# spindle_light.net
KiCad netlist of a schematic drawn in EAGLE
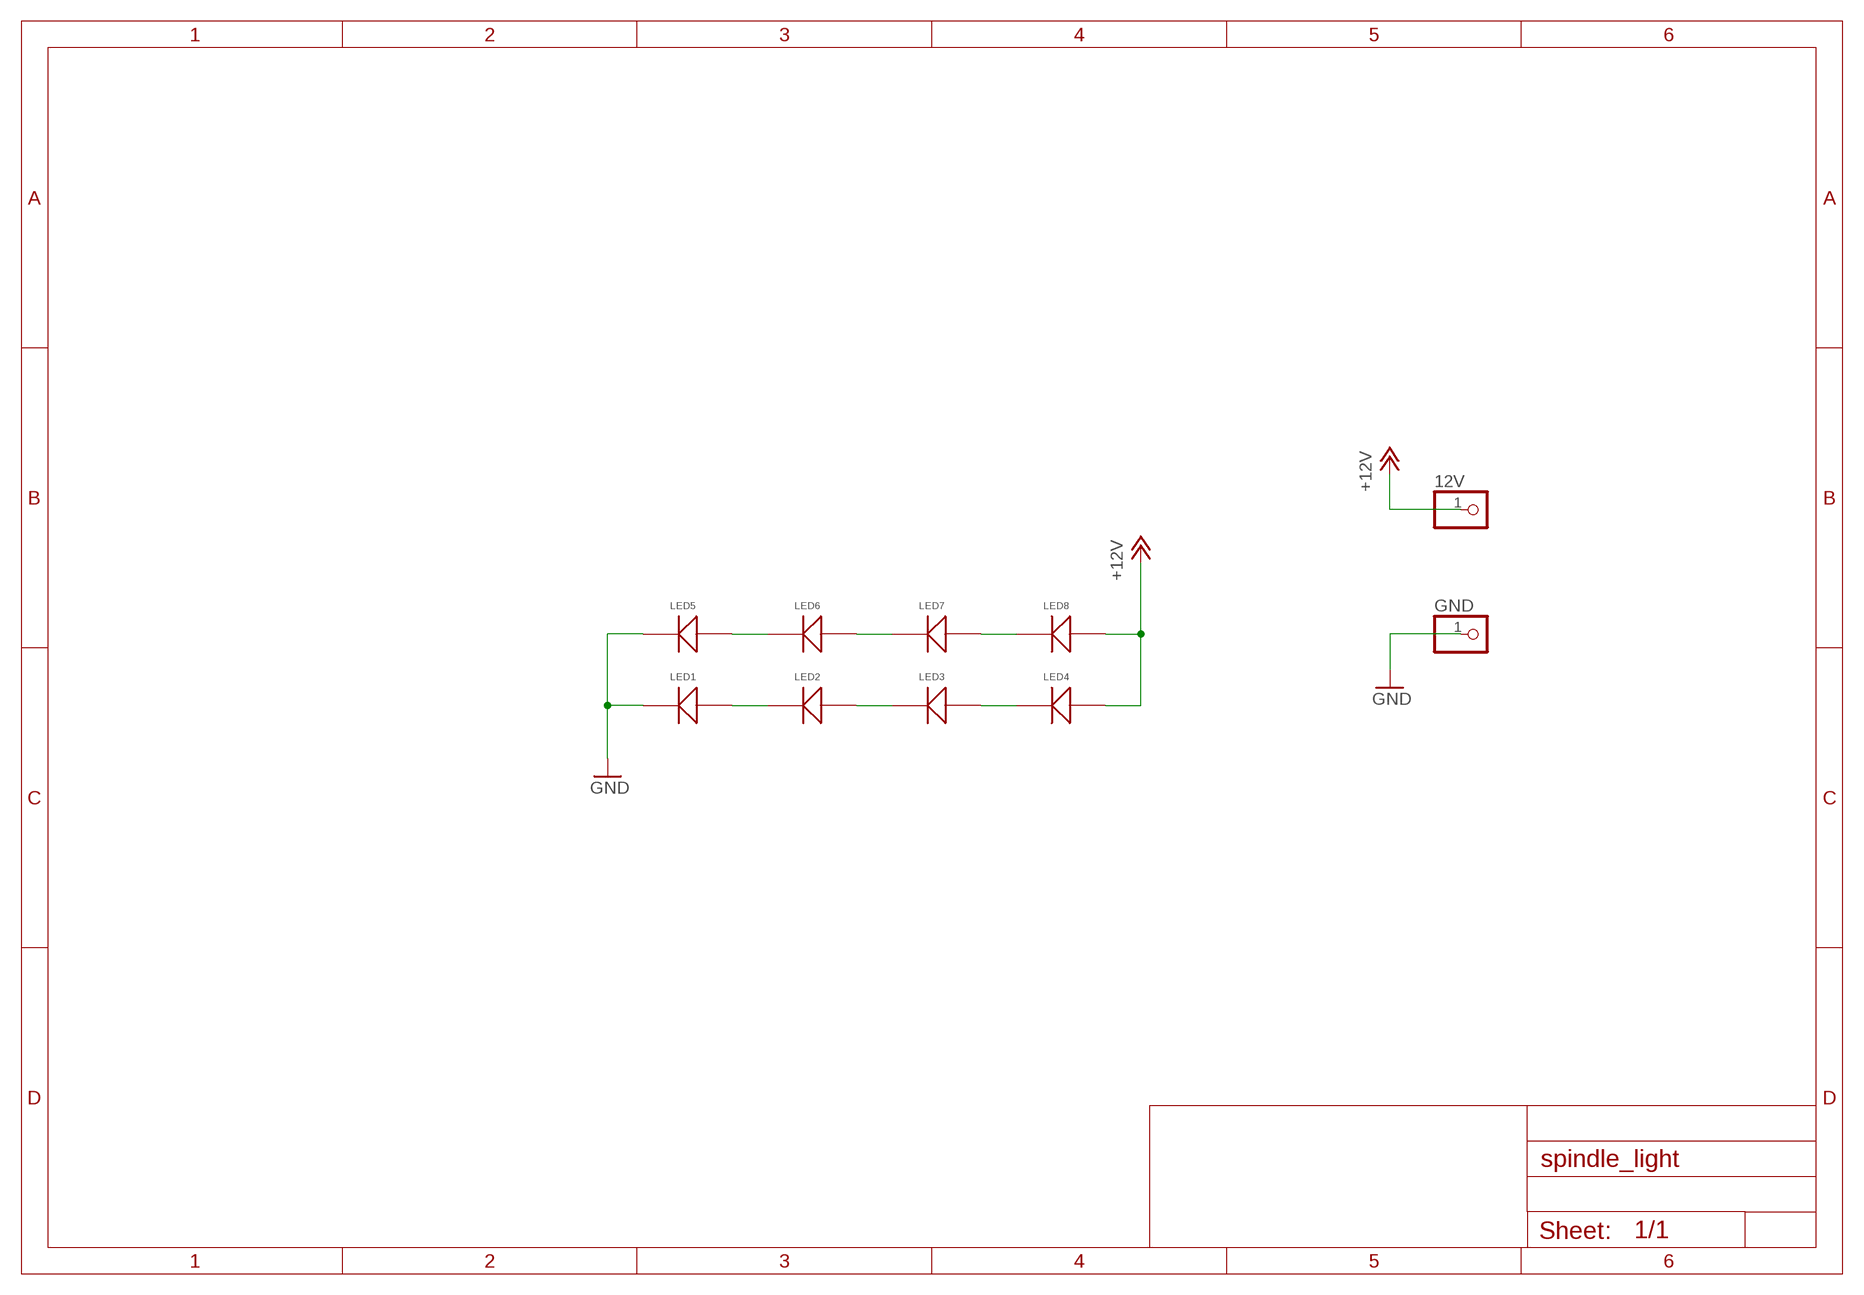
[diagram p0: schematic, sheet 1]

(export (version "E")
  (design (tool "Eeschema 10.0.6"))
  (components
    (comp (ref "12V")
      (value "PINHD-1X1")
      (footprint "eagle-import:1X01")
      (libsource (lib "eagle-import") (part "PINHD-1X1"))
    )
    (comp (ref "GND")
      (value "PINHD-1X1")
      (footprint "eagle-import:1X01")
      (libsource (lib "eagle-import") (part "PINHD-1X1"))
    )
    (comp (ref "LED1")
      (value "RF-45HA50DS-EE-Y")
      (footprint "eagle-import:5050LED")
      (libsource (lib "eagle-import") (part "RF-45HA50DS-EE-Y"))
    )
    (comp (ref "LED2")
      (value "RF-45HA50DS-EE-Y")
      (footprint "eagle-import:5050LED")
      (libsource (lib "eagle-import") (part "RF-45HA50DS-EE-Y"))
    )
    (comp (ref "LED3")
      (value "RF-45HA50DS-EE-Y")
      (footprint "eagle-import:5050LED")
      (libsource (lib "eagle-import") (part "RF-45HA50DS-EE-Y"))
    )
    (comp (ref "LED4")
      (value "RF-45HA50DS-EE-Y")
      (footprint "eagle-import:5050LED")
      (libsource (lib "eagle-import") (part "RF-45HA50DS-EE-Y"))
    )
    (comp (ref "LED5")
      (value "RF-45HA50DS-EE-Y")
      (footprint "eagle-import:5050LED")
      (libsource (lib "eagle-import") (part "RF-45HA50DS-EE-Y"))
    )
    (comp (ref "LED6")
      (value "RF-45HA50DS-EE-Y")
      (footprint "eagle-import:5050LED")
      (libsource (lib "eagle-import") (part "RF-45HA50DS-EE-Y"))
    )
    (comp (ref "LED7")
      (value "RF-45HA50DS-EE-Y")
      (footprint "eagle-import:5050LED")
      (libsource (lib "eagle-import") (part "RF-45HA50DS-EE-Y"))
    )
    (comp (ref "LED8")
      (value "RF-45HA50DS-EE-Y")
      (footprint "eagle-import:5050LED")
      (libsource (lib "eagle-import") (part "RF-45HA50DS-EE-Y"))
    )
  )
  (nets
    (net (code "1") (name "+12V") (class "Default")
      (node (ref "12V") (pin "1") (pinfunction "1_1") (pintype "passive"))
      (node (ref "LED4") (pin "P$4") (pinfunction "P$1_P$4") (pintype "bidirectional"))
      (node (ref "LED4") (pin "P$5") (pinfunction "P$1_P$5") (pintype "bidirectional"))
      (node (ref "LED4") (pin "P$6") (pinfunction "P$1_P$6") (pintype "bidirectional"))
      (node (ref "LED8") (pin "P$4") (pinfunction "P$1_P$4") (pintype "bidirectional"))
      (node (ref "LED8") (pin "P$5") (pinfunction "P$1_P$5") (pintype "bidirectional"))
      (node (ref "LED8") (pin "P$6") (pinfunction "P$1_P$6") (pintype "bidirectional"))
    )
    (net (code "2") (name "GND") (class "Default")
      (node (ref "GND") (pin "1") (pinfunction "1_1") (pintype "passive"))
      (node (ref "LED1") (pin "P$1") (pinfunction "P$2_P$1") (pintype "bidirectional"))
      (node (ref "LED1") (pin "P$2") (pinfunction "P$2_P$2") (pintype "bidirectional"))
      (node (ref "LED1") (pin "P$3") (pinfunction "P$2_P$3") (pintype "bidirectional"))
      (node (ref "LED5") (pin "P$1") (pinfunction "P$2_P$1") (pintype "bidirectional"))
      (node (ref "LED5") (pin "P$2") (pinfunction "P$2_P$2") (pintype "bidirectional"))
      (node (ref "LED5") (pin "P$3") (pinfunction "P$2_P$3") (pintype "bidirectional"))
    )
    (net (code "3") (name "Net-(LED1-P$1-PadP$4)") (class "Default")
      (node (ref "LED1") (pin "P$4") (pinfunction "P$1_P$4") (pintype "bidirectional"))
      (node (ref "LED1") (pin "P$5") (pinfunction "P$1_P$5") (pintype "bidirectional"))
      (node (ref "LED1") (pin "P$6") (pinfunction "P$1_P$6") (pintype "bidirectional"))
      (node (ref "LED2") (pin "P$1") (pinfunction "P$2_P$1") (pintype "bidirectional"))
      (node (ref "LED2") (pin "P$2") (pinfunction "P$2_P$2") (pintype "bidirectional"))
      (node (ref "LED2") (pin "P$3") (pinfunction "P$2_P$3") (pintype "bidirectional"))
    )
    (net (code "4") (name "Net-(LED2-P$1-PadP$4)") (class "Default")
      (node (ref "LED2") (pin "P$4") (pinfunction "P$1_P$4") (pintype "bidirectional"))
      (node (ref "LED2") (pin "P$5") (pinfunction "P$1_P$5") (pintype "bidirectional"))
      (node (ref "LED2") (pin "P$6") (pinfunction "P$1_P$6") (pintype "bidirectional"))
      (node (ref "LED3") (pin "P$1") (pinfunction "P$2_P$1") (pintype "bidirectional"))
      (node (ref "LED3") (pin "P$2") (pinfunction "P$2_P$2") (pintype "bidirectional"))
      (node (ref "LED3") (pin "P$3") (pinfunction "P$2_P$3") (pintype "bidirectional"))
    )
    (net (code "5") (name "Net-(LED3-P$1-PadP$4)") (class "Default")
      (node (ref "LED3") (pin "P$4") (pinfunction "P$1_P$4") (pintype "bidirectional"))
      (node (ref "LED3") (pin "P$5") (pinfunction "P$1_P$5") (pintype "bidirectional"))
      (node (ref "LED3") (pin "P$6") (pinfunction "P$1_P$6") (pintype "bidirectional"))
      (node (ref "LED4") (pin "P$1") (pinfunction "P$2_P$1") (pintype "bidirectional"))
      (node (ref "LED4") (pin "P$2") (pinfunction "P$2_P$2") (pintype "bidirectional"))
      (node (ref "LED4") (pin "P$3") (pinfunction "P$2_P$3") (pintype "bidirectional"))
    )
    (net (code "6") (name "Net-(LED5-P$1-PadP$4)") (class "Default")
      (node (ref "LED5") (pin "P$4") (pinfunction "P$1_P$4") (pintype "bidirectional"))
      (node (ref "LED5") (pin "P$5") (pinfunction "P$1_P$5") (pintype "bidirectional"))
      (node (ref "LED5") (pin "P$6") (pinfunction "P$1_P$6") (pintype "bidirectional"))
      (node (ref "LED6") (pin "P$1") (pinfunction "P$2_P$1") (pintype "bidirectional"))
      (node (ref "LED6") (pin "P$2") (pinfunction "P$2_P$2") (pintype "bidirectional"))
      (node (ref "LED6") (pin "P$3") (pinfunction "P$2_P$3") (pintype "bidirectional"))
    )
    (net (code "7") (name "Net-(LED6-P$1-PadP$4)") (class "Default")
      (node (ref "LED6") (pin "P$4") (pinfunction "P$1_P$4") (pintype "bidirectional"))
      (node (ref "LED6") (pin "P$5") (pinfunction "P$1_P$5") (pintype "bidirectional"))
      (node (ref "LED6") (pin "P$6") (pinfunction "P$1_P$6") (pintype "bidirectional"))
      (node (ref "LED7") (pin "P$1") (pinfunction "P$2_P$1") (pintype "bidirectional"))
      (node (ref "LED7") (pin "P$2") (pinfunction "P$2_P$2") (pintype "bidirectional"))
      (node (ref "LED7") (pin "P$3") (pinfunction "P$2_P$3") (pintype "bidirectional"))
    )
    (net (code "8") (name "Net-(LED7-P$1-PadP$4)") (class "Default")
      (node (ref "LED7") (pin "P$4") (pinfunction "P$1_P$4") (pintype "bidirectional"))
      (node (ref "LED7") (pin "P$5") (pinfunction "P$1_P$5") (pintype "bidirectional"))
      (node (ref "LED7") (pin "P$6") (pinfunction "P$1_P$6") (pintype "bidirectional"))
      (node (ref "LED8") (pin "P$1") (pinfunction "P$2_P$1") (pintype "bidirectional"))
      (node (ref "LED8") (pin "P$2") (pinfunction "P$2_P$2") (pintype "bidirectional"))
      (node (ref "LED8") (pin "P$3") (pinfunction "P$2_P$3") (pintype "bidirectional"))
    )
  )
)
